# Bank34.net
KiCad netlist of a schematic drawn in Altium Designer
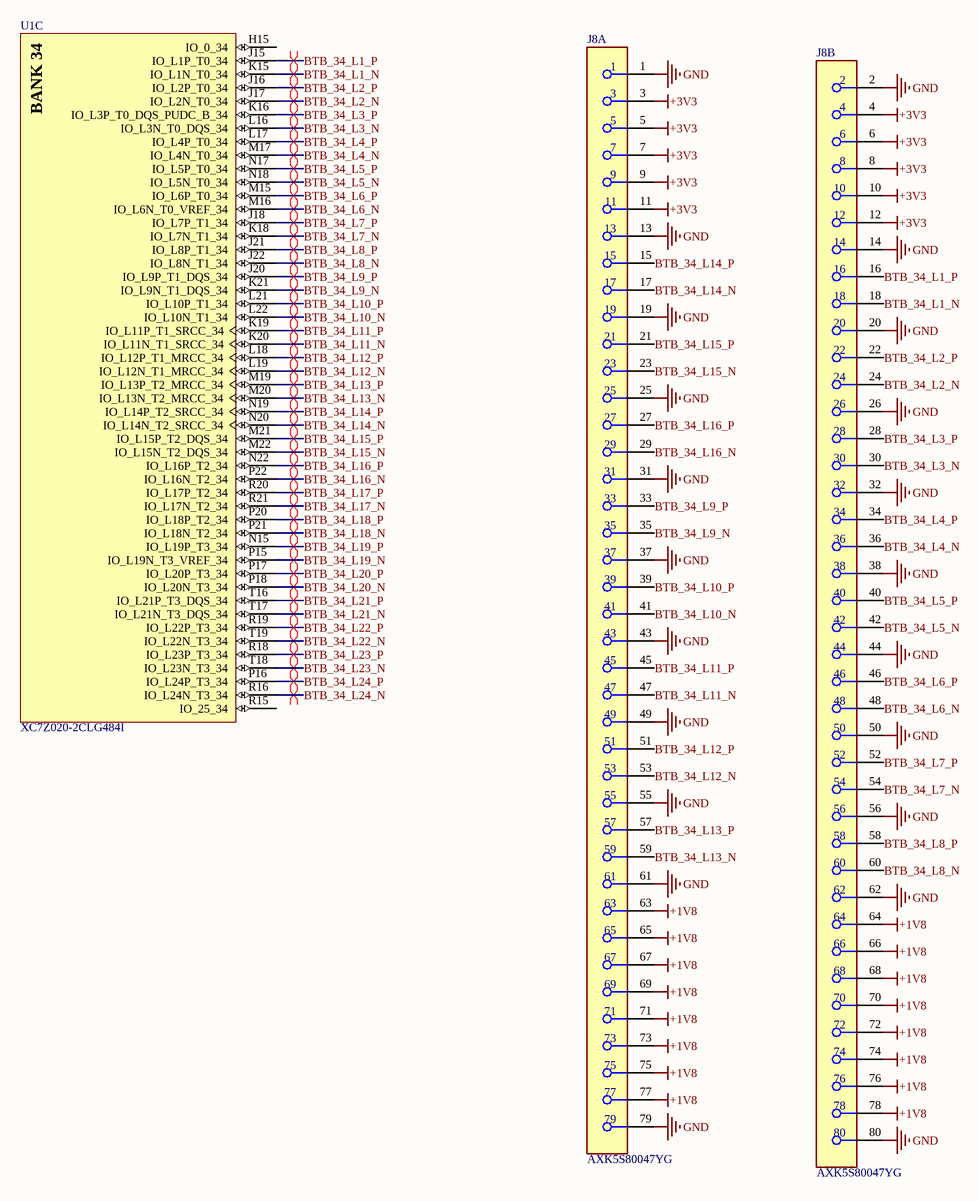
[diagram p0: Bank34.SchDoc]

(export (version "E")
  (design (tool "Eeschema 10.0.6"))
  (components
    (comp (ref "J8")
      (value "AXK5S80047YG")
      (footprint "FP-AXK5S80047YG-MFG")
      (description "CONN SOCKET BRD/BRD .5MM 80POS")
      (fields
        (field (name "OCTOPART") "https://octopart.com/axk5s80047yg-panasonic-7879921")
        (field (name "MANUFACTURER") "Panasonic")
      )
      (libsource (lib "Altium Content Vault") (part "54201cccd54d5375c727801065c3f31"))
    )
    (comp (ref "U1")
      (value "XC7Z020-2CLG484I")
      (footprint "CLG484")
      (fields (field (name "GENERIC PART NUMBER") "XC7Z020"))
      (libsource (lib "Altium Content Vault") (part "XNLX-XC7Z020-CLG484"))
    )
  )
  (nets
    (net (code "1") (name "+1V8") (class "Default")
      (node (ref "J8") (pin "63") (pinfunction "63_63") (pintype "passive"))
      (node (ref "J8") (pin "64") (pinfunction "64_64") (pintype "passive"))
      (node (ref "J8") (pin "65") (pinfunction "65_65") (pintype "passive"))
      (node (ref "J8") (pin "66") (pinfunction "66_66") (pintype "passive"))
      (node (ref "J8") (pin "67") (pinfunction "67_67") (pintype "passive"))
      (node (ref "J8") (pin "68") (pinfunction "68_68") (pintype "passive"))
      (node (ref "J8") (pin "69") (pinfunction "69_69") (pintype "passive"))
      (node (ref "J8") (pin "70") (pinfunction "70_70") (pintype "passive"))
      (node (ref "J8") (pin "71") (pinfunction "71_71") (pintype "passive"))
      (node (ref "J8") (pin "72") (pinfunction "72_72") (pintype "passive"))
      (node (ref "J8") (pin "73") (pinfunction "73_73") (pintype "passive"))
      (node (ref "J8") (pin "74") (pinfunction "74_74") (pintype "passive"))
      (node (ref "J8") (pin "75") (pinfunction "75_75") (pintype "passive"))
      (node (ref "J8") (pin "76") (pinfunction "76_76") (pintype "passive"))
      (node (ref "J8") (pin "77") (pinfunction "77_77") (pintype "passive"))
      (node (ref "J8") (pin "78") (pinfunction "78_78") (pintype "passive"))
    )
    (net (code "2") (name "+3V3") (class "Default")
      (node (ref "J8") (pin "10") (pinfunction "10_10") (pintype "passive"))
      (node (ref "J8") (pin "11") (pinfunction "11_11") (pintype "passive"))
      (node (ref "J8") (pin "12") (pinfunction "12_12") (pintype "passive"))
      (node (ref "J8") (pin "3") (pinfunction "3_3") (pintype "passive"))
      (node (ref "J8") (pin "4") (pinfunction "4_4") (pintype "passive"))
      (node (ref "J8") (pin "5") (pinfunction "5_5") (pintype "passive"))
      (node (ref "J8") (pin "6") (pinfunction "6_6") (pintype "passive"))
      (node (ref "J8") (pin "7") (pinfunction "7_7") (pintype "passive"))
      (node (ref "J8") (pin "8") (pinfunction "8_8") (pintype "passive"))
      (node (ref "J8") (pin "9") (pinfunction "9_9") (pintype "passive"))
    )
    (net (code "3") (name "/BTB_34_L1_N") (class "Default")
      (node (ref "J8") (pin "18") (pinfunction "18_18") (pintype "passive"))
      (node (ref "U1") (pin "K15") (pinfunction "IO_L1N_T0_34_K15") (pintype "bidirectional"))
    )
    (net (code "4") (name "/BTB_34_L1_P") (class "Default")
      (node (ref "J8") (pin "16") (pinfunction "16_16") (pintype "passive"))
      (node (ref "U1") (pin "J15") (pinfunction "IO_L1P_T0_34_J15") (pintype "bidirectional"))
    )
    (net (code "5") (name "/BTB_34_L2_N") (class "Default")
      (node (ref "J8") (pin "24") (pinfunction "24_24") (pintype "passive"))
      (node (ref "U1") (pin "J17") (pinfunction "IO_L2N_T0_34_J17") (pintype "bidirectional"))
    )
    (net (code "6") (name "/BTB_34_L2_P") (class "Default")
      (node (ref "J8") (pin "22") (pinfunction "22_22") (pintype "passive"))
      (node (ref "U1") (pin "J16") (pinfunction "IO_L2P_T0_34_J16") (pintype "bidirectional"))
    )
    (net (code "7") (name "/BTB_34_L3_N") (class "Default")
      (node (ref "J8") (pin "30") (pinfunction "30_30") (pintype "passive"))
      (node (ref "U1") (pin "L16") (pinfunction "IO_L3N_T0_DQS_34_L16") (pintype "bidirectional"))
    )
    (net (code "8") (name "/BTB_34_L3_P") (class "Default")
      (node (ref "J8") (pin "28") (pinfunction "28_28") (pintype "passive"))
      (node (ref "U1") (pin "K16") (pinfunction "IO_L3P_T0_DQS_PUDC_B_34_K16") (pintype "bidirectional"))
    )
    (net (code "9") (name "/BTB_34_L4_N") (class "Default")
      (node (ref "J8") (pin "36") (pinfunction "36_36") (pintype "passive"))
      (node (ref "U1") (pin "M17") (pinfunction "IO_L4N_T0_34_M17") (pintype "bidirectional"))
    )
    (net (code "10") (name "/BTB_34_L4_P") (class "Default")
      (node (ref "J8") (pin "34") (pinfunction "34_34") (pintype "passive"))
      (node (ref "U1") (pin "L17") (pinfunction "IO_L4P_T0_34_L17") (pintype "bidirectional"))
    )
    (net (code "11") (name "/BTB_34_L5_N") (class "Default")
      (node (ref "J8") (pin "42") (pinfunction "42_42") (pintype "passive"))
      (node (ref "U1") (pin "N18") (pinfunction "IO_L5N_T0_34_N18") (pintype "bidirectional"))
    )
    (net (code "12") (name "/BTB_34_L5_P") (class "Default")
      (node (ref "J8") (pin "40") (pinfunction "40_40") (pintype "passive"))
      (node (ref "U1") (pin "N17") (pinfunction "IO_L5P_T0_34_N17") (pintype "bidirectional"))
    )
    (net (code "13") (name "/BTB_34_L6_N") (class "Default")
      (node (ref "J8") (pin "48") (pinfunction "48_48") (pintype "passive"))
      (node (ref "U1") (pin "M16") (pinfunction "IO_L6N_T0_VREF_34_M16") (pintype "bidirectional"))
    )
    (net (code "14") (name "/BTB_34_L6_P") (class "Default")
      (node (ref "J8") (pin "46") (pinfunction "46_46") (pintype "passive"))
      (node (ref "U1") (pin "M15") (pinfunction "IO_L6P_T0_34_M15") (pintype "bidirectional"))
    )
    (net (code "15") (name "/BTB_34_L7_N") (class "Default")
      (node (ref "J8") (pin "54") (pinfunction "54_54") (pintype "passive"))
      (node (ref "U1") (pin "K18") (pinfunction "IO_L7N_T1_34_K18") (pintype "bidirectional"))
    )
    (net (code "16") (name "/BTB_34_L7_P") (class "Default")
      (node (ref "J8") (pin "52") (pinfunction "52_52") (pintype "passive"))
      (node (ref "U1") (pin "J18") (pinfunction "IO_L7P_T1_34_J18") (pintype "bidirectional"))
    )
    (net (code "17") (name "/BTB_34_L8_N") (class "Default")
      (node (ref "J8") (pin "60") (pinfunction "60_60") (pintype "passive"))
      (node (ref "U1") (pin "J22") (pinfunction "IO_L8N_T1_34_J22") (pintype "bidirectional"))
    )
    (net (code "18") (name "/BTB_34_L8_P") (class "Default")
      (node (ref "J8") (pin "58") (pinfunction "58_58") (pintype "passive"))
      (node (ref "U1") (pin "J21") (pinfunction "IO_L8P_T1_34_J21") (pintype "bidirectional"))
    )
    (net (code "19") (name "/BTB_34_L9_N") (class "Default")
      (node (ref "J8") (pin "35") (pinfunction "35_35") (pintype "passive"))
      (node (ref "U1") (pin "K21") (pinfunction "IO_L9N_T1_DQS_34_K21") (pintype "bidirectional"))
    )
    (net (code "20") (name "/BTB_34_L9_P") (class "Default")
      (node (ref "J8") (pin "33") (pinfunction "33_33") (pintype "passive"))
      (node (ref "U1") (pin "J20") (pinfunction "IO_L9P_T1_DQS_34_J20") (pintype "bidirectional"))
    )
    (net (code "21") (name "/BTB_34_L10_N") (class "Default")
      (node (ref "J8") (pin "41") (pinfunction "41_41") (pintype "passive"))
      (node (ref "U1") (pin "L22") (pinfunction "IO_L10N_T1_34_L22") (pintype "bidirectional"))
    )
    (net (code "22") (name "/BTB_34_L10_P") (class "Default")
      (node (ref "J8") (pin "39") (pinfunction "39_39") (pintype "passive"))
      (node (ref "U1") (pin "L21") (pinfunction "IO_L10P_T1_34_L21") (pintype "bidirectional"))
    )
    (net (code "23") (name "/BTB_34_L11_N") (class "Default")
      (node (ref "J8") (pin "47") (pinfunction "47_47") (pintype "passive"))
      (node (ref "U1") (pin "K20") (pinfunction "IO_L11N_T1_SRCC_34_K20") (pintype "bidirectional"))
    )
    (net (code "24") (name "/BTB_34_L11_P") (class "Default")
      (node (ref "J8") (pin "45") (pinfunction "45_45") (pintype "passive"))
      (node (ref "U1") (pin "K19") (pinfunction "IO_L11P_T1_SRCC_34_K19") (pintype "bidirectional"))
    )
    (net (code "25") (name "/BTB_34_L12_N") (class "Default")
      (node (ref "J8") (pin "53") (pinfunction "53_53") (pintype "passive"))
      (node (ref "U1") (pin "L19") (pinfunction "IO_L12N_T1_MRCC_34_L19") (pintype "bidirectional"))
    )
    (net (code "26") (name "/BTB_34_L12_P") (class "Default")
      (node (ref "J8") (pin "51") (pinfunction "51_51") (pintype "passive"))
      (node (ref "U1") (pin "L18") (pinfunction "IO_L12P_T1_MRCC_34_L18") (pintype "bidirectional"))
    )
    (net (code "27") (name "/BTB_34_L13_N") (class "Default")
      (node (ref "J8") (pin "59") (pinfunction "59_59") (pintype "passive"))
      (node (ref "U1") (pin "M20") (pinfunction "IO_L13N_T2_MRCC_34_M20") (pintype "bidirectional"))
    )
    (net (code "28") (name "/BTB_34_L13_P") (class "Default")
      (node (ref "J8") (pin "57") (pinfunction "57_57") (pintype "passive"))
      (node (ref "U1") (pin "M19") (pinfunction "IO_L13P_T2_MRCC_34_M19") (pintype "bidirectional"))
    )
    (net (code "29") (name "/BTB_34_L14_N") (class "Default")
      (node (ref "J8") (pin "17") (pinfunction "17_17") (pintype "passive"))
      (node (ref "U1") (pin "N20") (pinfunction "IO_L14N_T2_SRCC_34_N20") (pintype "bidirectional"))
    )
    (net (code "30") (name "/BTB_34_L14_P") (class "Default")
      (node (ref "J8") (pin "15") (pinfunction "15_15") (pintype "passive"))
      (node (ref "U1") (pin "N19") (pinfunction "IO_L14P_T2_SRCC_34_N19") (pintype "bidirectional"))
    )
    (net (code "31") (name "/BTB_34_L15_N") (class "Default")
      (node (ref "J8") (pin "23") (pinfunction "23_23") (pintype "passive"))
      (node (ref "U1") (pin "M22") (pinfunction "IO_L15N_T2_DQS_34_M22") (pintype "bidirectional"))
    )
    (net (code "32") (name "/BTB_34_L15_P") (class "Default")
      (node (ref "J8") (pin "21") (pinfunction "21_21") (pintype "passive"))
      (node (ref "U1") (pin "M21") (pinfunction "IO_L15P_T2_DQS_34_M21") (pintype "bidirectional"))
    )
    (net (code "33") (name "/BTB_34_L16_N") (class "Default")
      (node (ref "J8") (pin "29") (pinfunction "29_29") (pintype "passive"))
      (node (ref "U1") (pin "P22") (pinfunction "IO_L16N_T2_34_P22") (pintype "bidirectional"))
    )
    (net (code "34") (name "/BTB_34_L16_P") (class "Default")
      (node (ref "J8") (pin "27") (pinfunction "27_27") (pintype "passive"))
      (node (ref "U1") (pin "N22") (pinfunction "IO_L16P_T2_34_N22") (pintype "bidirectional"))
    )
    (net (code "35") (name "/BTB_34_L17_N") (class "Default")
      (node (ref "U1") (pin "R21") (pinfunction "IO_L17N_T2_34_R21") (pintype "bidirectional"))
    )
    (net (code "36") (name "/BTB_34_L17_P") (class "Default")
      (node (ref "U1") (pin "R20") (pinfunction "IO_L17P_T2_34_R20") (pintype "bidirectional"))
    )
    (net (code "37") (name "/BTB_34_L18_N") (class "Default")
      (node (ref "U1") (pin "P21") (pinfunction "IO_L18N_T2_34_P21") (pintype "bidirectional"))
    )
    (net (code "38") (name "/BTB_34_L18_P") (class "Default")
      (node (ref "U1") (pin "P20") (pinfunction "IO_L18P_T2_34_P20") (pintype "bidirectional"))
    )
    (net (code "39") (name "/BTB_34_L19_N") (class "Default")
      (node (ref "U1") (pin "P15") (pinfunction "IO_L19N_T3_VREF_34_P15") (pintype "bidirectional"))
    )
    (net (code "40") (name "/BTB_34_L19_P") (class "Default")
      (node (ref "U1") (pin "N15") (pinfunction "IO_L19P_T3_34_N15") (pintype "bidirectional"))
    )
    (net (code "41") (name "/BTB_34_L20_N") (class "Default")
      (node (ref "U1") (pin "P18") (pinfunction "IO_L20N_T3_34_P18") (pintype "bidirectional"))
    )
    (net (code "42") (name "/BTB_34_L20_P") (class "Default")
      (node (ref "U1") (pin "P17") (pinfunction "IO_L20P_T3_34_P17") (pintype "bidirectional"))
    )
    (net (code "43") (name "/BTB_34_L21_N") (class "Default")
      (node (ref "U1") (pin "T17") (pinfunction "IO_L21N_T3_DQS_34_T17") (pintype "bidirectional"))
    )
    (net (code "44") (name "/BTB_34_L21_P") (class "Default")
      (node (ref "U1") (pin "T16") (pinfunction "IO_L21P_T3_DQS_34_T16") (pintype "bidirectional"))
    )
    (net (code "45") (name "/BTB_34_L22_N") (class "Default")
      (node (ref "U1") (pin "T19") (pinfunction "IO_L22N_T3_34_T19") (pintype "bidirectional"))
    )
    (net (code "46") (name "/BTB_34_L22_P") (class "Default")
      (node (ref "U1") (pin "R19") (pinfunction "IO_L22P_T3_34_R19") (pintype "bidirectional"))
    )
    (net (code "47") (name "/BTB_34_L23_N") (class "Default")
      (node (ref "U1") (pin "T18") (pinfunction "IO_L23N_T3_34_T18") (pintype "bidirectional"))
    )
    (net (code "48") (name "/BTB_34_L23_P") (class "Default")
      (node (ref "U1") (pin "R18") (pinfunction "IO_L23P_T3_34_R18") (pintype "bidirectional"))
    )
    (net (code "49") (name "/BTB_34_L24_N") (class "Default")
      (node (ref "U1") (pin "R16") (pinfunction "IO_L24N_T3_34_R16") (pintype "bidirectional"))
    )
    (net (code "50") (name "/BTB_34_L24_P") (class "Default")
      (node (ref "U1") (pin "P16") (pinfunction "IO_L24P_T3_34_P16") (pintype "bidirectional"))
    )
    (net (code "51") (name "GND") (class "Default")
      (node (ref "J8") (pin "1") (pinfunction "1_1") (pintype "passive"))
      (node (ref "J8") (pin "13") (pinfunction "13_13") (pintype "passive"))
      (node (ref "J8") (pin "14") (pinfunction "14_14") (pintype "passive"))
      (node (ref "J8") (pin "19") (pinfunction "19_19") (pintype "passive"))
      (node (ref "J8") (pin "2") (pinfunction "2_2") (pintype "passive"))
      (node (ref "J8") (pin "20") (pinfunction "20_20") (pintype "passive"))
      (node (ref "J8") (pin "25") (pinfunction "25_25") (pintype "passive"))
      (node (ref "J8") (pin "26") (pinfunction "26_26") (pintype "passive"))
      (node (ref "J8") (pin "31") (pinfunction "31_31") (pintype "passive"))
      (node (ref "J8") (pin "32") (pinfunction "32_32") (pintype "passive"))
      (node (ref "J8") (pin "37") (pinfunction "37_37") (pintype "passive"))
      (node (ref "J8") (pin "38") (pinfunction "38_38") (pintype "passive"))
      (node (ref "J8") (pin "43") (pinfunction "43_43") (pintype "passive"))
      (node (ref "J8") (pin "44") (pinfunction "44_44") (pintype "passive"))
      (node (ref "J8") (pin "49") (pinfunction "49_49") (pintype "passive"))
      (node (ref "J8") (pin "50") (pinfunction "50_50") (pintype "passive"))
      (node (ref "J8") (pin "55") (pinfunction "55_55") (pintype "passive"))
      (node (ref "J8") (pin "56") (pinfunction "56_56") (pintype "passive"))
      (node (ref "J8") (pin "61") (pinfunction "61_61") (pintype "passive"))
      (node (ref "J8") (pin "62") (pinfunction "62_62") (pintype "passive"))
      (node (ref "J8") (pin "79") (pinfunction "79_79") (pintype "passive"))
      (node (ref "J8") (pin "80") (pinfunction "80_80") (pintype "passive"))
    )
    (net (code "52") (name "unconnected-(U1C-IO_0_34-PadH15)") (class "Default")
      (node (ref "U1") (pin "H15") (pinfunction "IO_0_34_H15") (pintype "bidirectional"))
    )
    (net (code "53") (name "unconnected-(U1C-IO_25_34-PadR15)") (class "Default")
      (node (ref "U1") (pin "R15") (pinfunction "IO_25_34_R15") (pintype "bidirectional"))
    )
  )
)
